# COMM_LEVEL_SHIFTER.net
KiCad netlist of a schematic drawn in Altium Designer
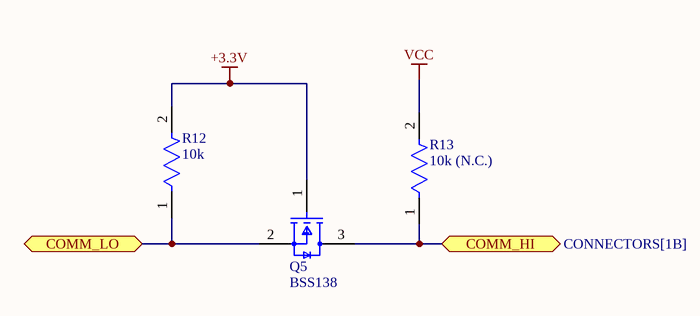
[diagram p0: COMM LEVEL SHIFTER.SchDoc]

(export (version "E")
  (design (tool "Eeschema 10.0.6"))
  (components
    (comp (ref "Q5")
      (value "BSS138")
      (footprint "FP-318-08-IPC_B")
      (description "MOSFET N-CH 50V 220MA SOT-23")
      (fields (field (name "LCSC PART #") "C5224260"))
      (libsource (lib "Altium Content Vault") (part "3b9c635fedb024a5347a57b145af9cc"))
    )
    (comp (ref "R12")
      (value "10k")
      (footprint "FP-RP731J-MFG")
      (fields
        (field (name "MANUFACTURER") "TE Connectivity")
        (field (name "OCTOPART") "https://octopart.com/rp73d1j8r45btdg-te+connectivity-42630912")
        (field (name "MANUFACTURER PART NUMBER") "RP73D1J8R45BTDG")
      )
      (libsource (lib "Altium Content Vault") (part "1029c3af85768c4190bb7ad29bc67b5"))
    )
    (comp (ref "R13")
      (value "10k (N.C.)")
      (footprint "FP-RP731J-MFG")
      (fields
        (field (name "MANUFACTURER") "TE Connectivity")
        (field (name "OCTOPART") "https://octopart.com/rp73d1j8r45btdg-te+connectivity-42630912")
        (field (name "MANUFACTURER PART NUMBER") "RP73D1J8R45BTDG")
      )
      (libsource (lib "Altium Content Vault") (part "1029c3af85768c4190bb7ad29bc67b5"))
    )
  )
  (nets
    (net (code "1") (name "+3.3V") (class "Default")
      (node (ref "Q5") (pin "1") (pinfunction "G_1") (pintype "passive"))
      (node (ref "R12") (pin "2") (pinfunction "2_2") (pintype "passive"))
    )
    (net (code "2") (name "/COMM_HI") (class "Default")
      (node (ref "Q5") (pin "3") (pinfunction "D_3") (pintype "passive"))
      (node (ref "R13") (pin "1") (pinfunction "1_1") (pintype "passive"))
    )
    (net (code "3") (name "/COMM_LO") (class "Default")
      (node (ref "Q5") (pin "2") (pinfunction "S_2") (pintype "passive"))
      (node (ref "R12") (pin "1") (pinfunction "1_1") (pintype "passive"))
    )
    (net (code "4") (name "VCC") (class "Default")
      (node (ref "R13") (pin "2") (pinfunction "2_2") (pintype "passive"))
    )
  )
)
